# Mini-32BOT_Rev_A.net
KiCad netlist of a schematic drawn in EAGLE
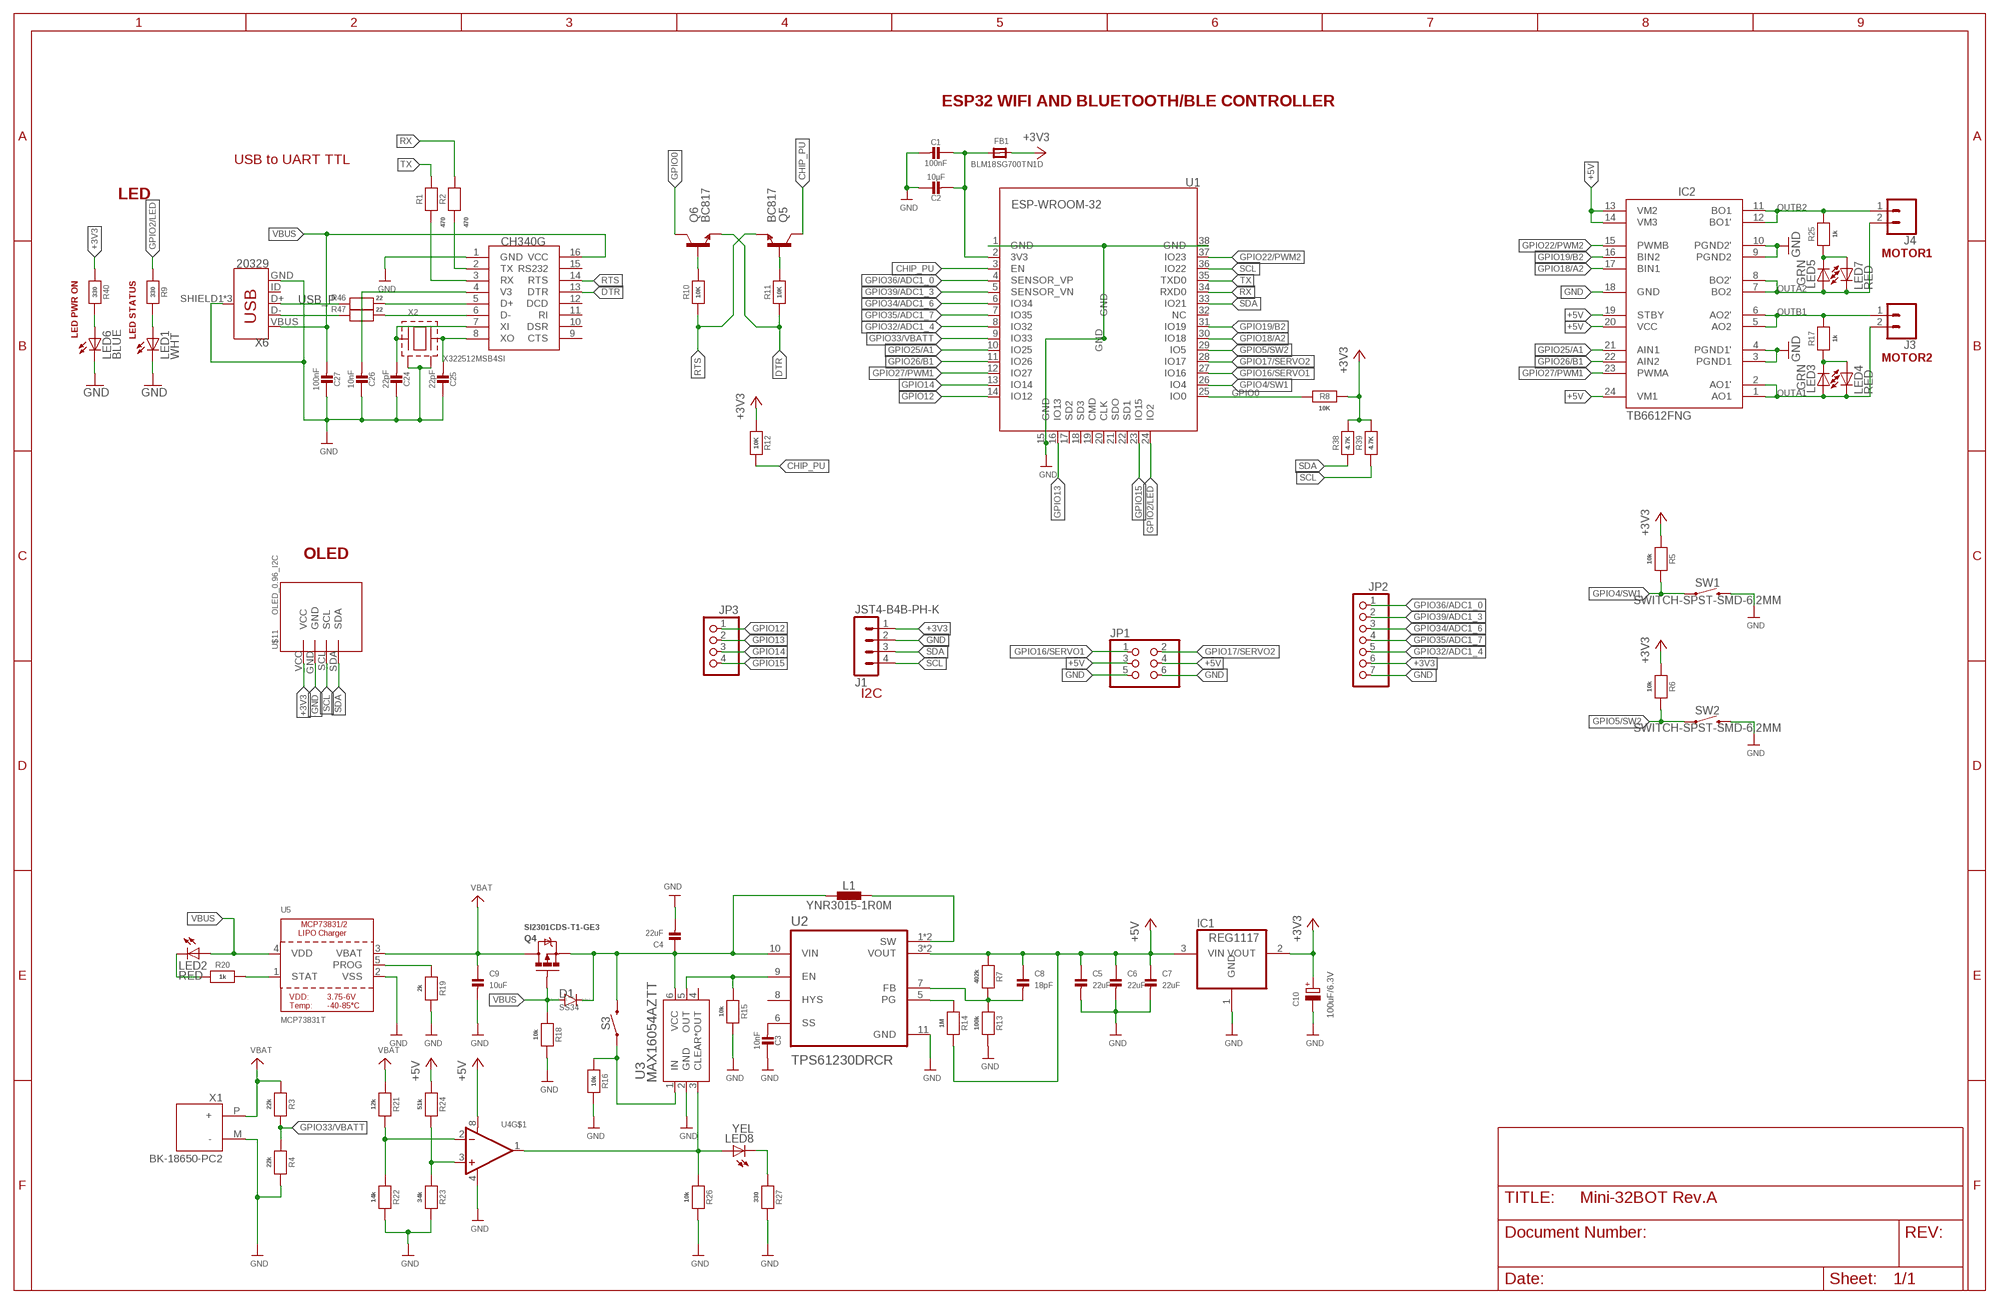
[diagram p0: schematic, sheet 1]

(export (version "E")
  (design (tool "Eeschema 10.0.6"))
  (components
    (comp (ref "C1")
      (value "100nF")
      (footprint "eagle-import:0603")
      (libsource (lib "eagle-import") (part "CAP_CERAMIC0603"))
    )
    (comp (ref "C2")
      (value "10µF")
      (footprint "eagle-import:0805")
      (libsource (lib "eagle-import") (part "CAP_CERAMIC0805"))
    )
    (comp (ref "C3")
      (value "10nF")
      (footprint "eagle-import:0603")
      (libsource (lib "eagle-import") (part "CAP_CERAMIC0603"))
    )
    (comp (ref "C4")
      (value "22uF")
      (footprint "eagle-import:0805")
      (libsource (lib "eagle-import") (part "CAP_CERAMIC0805"))
    )
    (comp (ref "C5")
      (value "22uF")
      (footprint "eagle-import:0805")
      (libsource (lib "eagle-import") (part "CAP_CERAMIC0805"))
    )
    (comp (ref "C6")
      (value "22uF")
      (footprint "eagle-import:0805")
      (libsource (lib "eagle-import") (part "CAP_CERAMIC0805"))
    )
    (comp (ref "C7")
      (value "22uF")
      (footprint "eagle-import:0805")
      (libsource (lib "eagle-import") (part "CAP_CERAMIC0805"))
    )
    (comp (ref "C8")
      (value "18pF")
      (footprint "eagle-import:0603")
      (libsource (lib "eagle-import") (part "CAP_CERAMIC0603"))
    )
    (comp (ref "C9")
      (value "10uF")
      (footprint "eagle-import:0805")
      (libsource (lib "eagle-import") (part "CAP_CERAMIC0805"))
    )
    (comp (ref "C10")
      (value "100uF/6.3V")
      (footprint "eagle-import:CT3528")
      (libsource (lib "eagle-import") (part "CPOL-EUCT3528"))
    )
    (comp (ref "C24")
      (value "22pF")
      (footprint "eagle-import:0603")
      (libsource (lib "eagle-import") (part "CAP_CERAMIC0603"))
    )
    (comp (ref "C25")
      (value "22pF")
      (footprint "eagle-import:0603")
      (libsource (lib "eagle-import") (part "CAP_CERAMIC0603"))
    )
    (comp (ref "C26")
      (value "10nF")
      (footprint "eagle-import:0603")
      (libsource (lib "eagle-import") (part "CAP_CERAMIC0603"))
    )
    (comp (ref "C27")
      (value "100nF")
      (footprint "eagle-import:0603")
      (libsource (lib "eagle-import") (part "CAP_CERAMIC0603"))
    )
    (comp (ref "D1")
      (value "SS34")
      (footprint "eagle-import:DO-214AC")
      (libsource (lib "eagle-import") (part "DIODE-DO-214AC"))
    )
    (comp (ref "FB1")
      (value "BLM18SG700TN1D")
      (footprint "eagle-import:_0603")
      (libsource (lib "eagle-import") (part "FERRITE_0603"))
    )
    (comp (ref "IC1")
      (value "REG1117")
      (footprint "eagle-import:SOT223")
      (libsource (lib "eagle-import") (part "REG1117"))
    )
    (comp (ref "IC2")
      (value "TB6612FNG")
      (footprint "eagle-import:SSOP24")
      (libsource (lib "eagle-import") (part "TB6612FNG"))
    )
    (comp (ref "J1")
      (value "JST4-B4B-PH-K")
      (footprint "eagle-import:JST_B4B-PH-K")
      (libsource (lib "eagle-import") (part "JST4-B4B-PH-K"))
    )
    (comp (ref "J3")
      (value "CONN_023.5MM")
      (footprint "eagle-import:SCREWTERMINAL-3.5MM-2")
      (libsource (lib "eagle-import") (part "CONN_023.5MM"))
    )
    (comp (ref "J4")
      (value "CONN_023.5MM")
      (footprint "eagle-import:SCREWTERMINAL-3.5MM-2")
      (libsource (lib "eagle-import") (part "CONN_023.5MM"))
    )
    (comp (ref "JP1")
      (value "PINHD-2X03_2.54")
      (footprint "eagle-import:2X03")
      (libsource (lib "eagle-import") (part "PINHD-2X03_2.54"))
    )
    (comp (ref "JP2")
      (value "PINHD-1X07_2.54-S")
      (footprint "eagle-import:1X07-S")
      (libsource (lib "eagle-import") (part "PINHD-1X07_2.54-S"))
    )
    (comp (ref "JP3")
      (value "PINHD-1X04_2.54-S")
      (footprint "eagle-import:1X04-S")
      (libsource (lib "eagle-import") (part "PINHD-1X04_2.54-S"))
    )
    (comp (ref "L1")
      (value "YNR3015-1R0M")
      (footprint "eagle-import:L_NR40XX")
      (libsource (lib "eagle-import") (part "INDUCTOR-NR40XX"))
    )
    (comp (ref "LED1")
      (value "WHT")
      (footprint "eagle-import:CHIP-LED0805")
      (libsource (lib "eagle-import") (part "LEDCHIP-LED0805"))
    )
    (comp (ref "LED2")
      (value "RED")
      (footprint "eagle-import:CHIP-LED0805")
      (libsource (lib "eagle-import") (part "LEDCHIP-LED0805"))
    )
    (comp (ref "LED3")
      (value "GRN")
      (footprint "eagle-import:CHIP-LED0805")
      (libsource (lib "eagle-import") (part "LEDCHIP-LED0805"))
    )
    (comp (ref "LED4")
      (value "RED")
      (footprint "eagle-import:CHIP-LED0805")
      (libsource (lib "eagle-import") (part "LEDCHIP-LED0805"))
    )
    (comp (ref "LED5")
      (value "GRN")
      (footprint "eagle-import:CHIP-LED0805")
      (libsource (lib "eagle-import") (part "LEDCHIP-LED0805"))
    )
    (comp (ref "LED6")
      (value "BLUE")
      (footprint "eagle-import:CHIP-LED0805")
      (libsource (lib "eagle-import") (part "LEDCHIP-LED0805"))
    )
    (comp (ref "LED7")
      (value "RED")
      (footprint "eagle-import:CHIP-LED0805")
      (libsource (lib "eagle-import") (part "LEDCHIP-LED0805"))
    )
    (comp (ref "LED8")
      (value "YEL")
      (footprint "eagle-import:CHIP-LED0805")
      (libsource (lib "eagle-import") (part "LEDCHIP-LED0805"))
    )
    (comp (ref "Q4")
      (value "SI2301CDS-T1-GE3")
      (footprint "eagle-import:SOT23-3")
      (libsource (lib "eagle-import") (part "MOSFET-PCHANNELDMG2307L"))
    )
    (comp (ref "Q5")
      (value "BC817")
      (footprint "eagle-import:SOT23-3")
      (libsource (lib "eagle-import") (part "TRANSISTOR_NPNSOT23-3"))
    )
    (comp (ref "Q6")
      (value "BC817")
      (footprint "eagle-import:SOT23-3")
      (libsource (lib "eagle-import") (part "TRANSISTOR_NPNSOT23-3"))
    )
    (comp (ref "R1")
      (value "470")
      (footprint "eagle-import:0603")
      (libsource (lib "eagle-import") (part "RESISTOR0603"))
    )
    (comp (ref "R2")
      (value "470")
      (footprint "eagle-import:0603")
      (libsource (lib "eagle-import") (part "RESISTOR0603"))
    )
    (comp (ref "R3")
      (value "22k")
      (footprint "eagle-import:0603")
      (libsource (lib "eagle-import") (part "RESISTOR0603"))
    )
    (comp (ref "R4")
      (value "22k")
      (footprint "eagle-import:0603")
      (libsource (lib "eagle-import") (part "RESISTOR0603"))
    )
    (comp (ref "R5")
      (value "10k")
      (footprint "eagle-import:0603")
      (libsource (lib "eagle-import") (part "RESISTOR0603"))
    )
    (comp (ref "R6")
      (value "10k")
      (footprint "eagle-import:0603")
      (libsource (lib "eagle-import") (part "RESISTOR0603"))
    )
    (comp (ref "R7")
      (value "402k")
      (footprint "eagle-import:0603")
      (libsource (lib "eagle-import") (part "RESISTOR0603"))
    )
    (comp (ref "R8")
      (value "10K")
      (footprint "eagle-import:0603")
      (libsource (lib "eagle-import") (part "RESISTOR0603"))
    )
    (comp (ref "R9")
      (value "330")
      (footprint "eagle-import:0603")
      (libsource (lib "eagle-import") (part "RESISTOR0603"))
    )
    (comp (ref "R10")
      (value "10K")
      (footprint "eagle-import:0603")
      (libsource (lib "eagle-import") (part "RESISTOR0603"))
    )
    (comp (ref "R11")
      (value "10K")
      (footprint "eagle-import:0603")
      (libsource (lib "eagle-import") (part "RESISTOR0603"))
    )
    (comp (ref "R12")
      (value "10K")
      (footprint "eagle-import:0603")
      (libsource (lib "eagle-import") (part "RESISTOR0603"))
    )
    (comp (ref "R13")
      (value "100k")
      (footprint "eagle-import:0603")
      (libsource (lib "eagle-import") (part "RESISTOR0603"))
    )
    (comp (ref "R14")
      (value "1M")
      (footprint "eagle-import:0603")
      (libsource (lib "eagle-import") (part "RESISTOR0603"))
    )
    (comp (ref "R15")
      (value "10k")
      (footprint "eagle-import:0603")
      (libsource (lib "eagle-import") (part "RESISTOR0603"))
    )
    (comp (ref "R16")
      (value "10k")
      (footprint "eagle-import:0603")
      (libsource (lib "eagle-import") (part "RESISTOR0603"))
    )
    (comp (ref "R17")
      (value "1k")
      (footprint "eagle-import:0603")
      (libsource (lib "eagle-import") (part "RESISTOR0603"))
    )
    (comp (ref "R18")
      (value "10k")
      (footprint "eagle-import:0603")
      (libsource (lib "eagle-import") (part "RESISTOR0603"))
    )
    (comp (ref "R19")
      (value "2k")
      (footprint "eagle-import:0603")
      (libsource (lib "eagle-import") (part "RESISTOR0603"))
    )
    (comp (ref "R20")
      (value "1k")
      (footprint "eagle-import:0603")
      (libsource (lib "eagle-import") (part "RESISTOR0603"))
    )
    (comp (ref "R21")
      (value "12k")
      (footprint "eagle-import:0603")
      (libsource (lib "eagle-import") (part "RESISTOR0603"))
    )
    (comp (ref "R22")
      (value "14k")
      (footprint "eagle-import:0603")
      (libsource (lib "eagle-import") (part "RESISTOR0603"))
    )
    (comp (ref "R23")
      (value "34k")
      (footprint "eagle-import:0603")
      (libsource (lib "eagle-import") (part "RESISTOR0603"))
    )
    (comp (ref "R24")
      (value "51k")
      (footprint "eagle-import:0603")
      (libsource (lib "eagle-import") (part "RESISTOR0603"))
    )
    (comp (ref "R25")
      (value "1k")
      (footprint "eagle-import:0603")
      (libsource (lib "eagle-import") (part "RESISTOR0603"))
    )
    (comp (ref "R26")
      (value "10k")
      (footprint "eagle-import:0603")
      (libsource (lib "eagle-import") (part "RESISTOR0603"))
    )
    (comp (ref "R27")
      (value "330")
      (footprint "eagle-import:0603")
      (libsource (lib "eagle-import") (part "RESISTOR0603"))
    )
    (comp (ref "R38")
      (value "4.7K")
      (footprint "eagle-import:0603")
      (libsource (lib "eagle-import") (part "RESISTOR0603"))
    )
    (comp (ref "R39")
      (value "4.7K")
      (footprint "eagle-import:0603")
      (libsource (lib "eagle-import") (part "RESISTOR0603"))
    )
    (comp (ref "R40")
      (value "330")
      (footprint "eagle-import:0603")
      (libsource (lib "eagle-import") (part "RESISTOR0603"))
    )
    (comp (ref "R46")
      (value "22")
      (footprint "eagle-import:0603")
      (libsource (lib "eagle-import") (part "RESISTOR0603"))
    )
    (comp (ref "R47")
      (value "22")
      (footprint "eagle-import:0603")
      (libsource (lib "eagle-import") (part "RESISTOR0603"))
    )
    (comp (ref "S3")
      (value "MOMENTARY-SWITCH-SPST-PTH-RIGHT-ANGLE-KIT")
      (footprint "eagle-import:TACTILE_SWITCH_PTH_RIGHT_ANGLE_KIT")
      (libsource (lib "eagle-import") (part "MOMENTARY-SWITCH-SPST-PTH-RIGHT-ANGLE-KIT"))
    )
    (comp (ref "SW1")
      (value "SWITCH-SPST-SMD-6.2MM")
      (footprint "eagle-import:TACTILE_SWITCH_SMD_6.2MM_TALL")
      (libsource (lib "eagle-import") (part "MOMENTARY-SWITCH-SPST-SMD-6.2MM-TALL"))
    )
    (comp (ref "SW2")
      (value "SWITCH-SPST-SMD-6.2MM")
      (footprint "eagle-import:TACTILE_SWITCH_SMD_6.2MM_TALL")
      (libsource (lib "eagle-import") (part "MOMENTARY-SWITCH-SPST-SMD-6.2MM-TALL"))
    )
    (comp (ref "U$11")
      (value "OLED_0.96_I2C")
      (footprint "eagle-import:OLED_0.96_I2C")
      (libsource (lib "eagle-import") (part "OLED_0.96_I2C"))
    )
    (comp (ref "U$24")
      (value "CH340G")
      (footprint "eagle-import:SOIC16")
      (libsource (lib "eagle-import") (part "CH340G"))
    )
    (comp (ref "U1")
      (value "ESP-WROOM-32")
      (footprint "eagle-import:ESP-WROOM-32")
      (libsource (lib "eagle-import") (part "ESP-WROOM-32"))
    )
    (comp (ref "U2")
      (value "TPS61230DRCR")
      (footprint "eagle-import:SON50P300X300X100-11N")
      (fields (field (name "MF") "Texas Instruments"))
      (libsource (lib "eagle-import") (part "TPS61230DRCR"))
    )
    (comp (ref "U3")
      (value "MAX16054AZTT")
      (footprint "eagle-import:21-0114C")
      (fields (field (name "MF") "Maxim Integrated") (field (name "MP") "MAX16054AZT+"))
      (libsource (lib "eagle-import") (part "MAX16054AZTT"))
    )
    (comp (ref "U4")
      (value "LM358")
      (footprint "eagle-import:SOIC8_150MIL")
      (libsource (lib "eagle-import") (part "LM358"))
    )
    (comp (ref "U5")
      (value "MCP73831T")
      (footprint "eagle-import:SOT23-5")
      (libsource (lib "eagle-import") (part "MCP73831/2"))
    )
    (comp (ref "X1")
      (value "BK-18650-PC2")
      (footprint "eagle-import:MPD_BK-18650-PC2")
      (fields (field (name "MF") "MPD _Memory"))
      (libsource (lib "eagle-import") (part "BK-18650-PC2"))
    )
    (comp (ref "X2")
      (value "X322512MSB4SI")
      (footprint "eagle-import:X3225_4P")
      (libsource (lib "eagle-import") (part "306010049_XTAL_16MHZ-3225_4P"))
    )
    (comp (ref "X6")
      (value "20329")
      (footprint "eagle-import:USB-B-MICRO-SMD")
      (libsource (lib "eagle-import") (part "USB_MICRO-B_FEMALE-SMT"))
    )
  )
  (nets
    (net (code "1") (name "+3V3") (class "Default")
      (node (ref "C10") (pin "+") (pinfunction "+_+") (pintype "passive"))
      (node (ref "FB1") (pin "2") (pinfunction "P$2_2") (pintype "passive"))
      (node (ref "IC1") (pin "2") (pinfunction "VOUT_2") (pintype "output"))
      (node (ref "J1") (pin "1") (pinfunction "1_1") (pintype "passive"))
      (node (ref "JP2") (pin "6") (pinfunction "6_6") (pintype "passive"))
      (node (ref "R12") (pin "1") (pinfunction "1_1") (pintype "passive"))
      (node (ref "R38") (pin "2") (pinfunction "2_2") (pintype "passive"))
      (node (ref "R39") (pin "2") (pinfunction "2_2") (pintype "passive"))
      (node (ref "R40") (pin "1") (pinfunction "1_1") (pintype "passive"))
      (node (ref "R5") (pin "1") (pinfunction "1_1") (pintype "passive"))
      (node (ref "R6") (pin "1") (pinfunction "1_1") (pintype "passive"))
      (node (ref "R8") (pin "2") (pinfunction "2_2") (pintype "passive"))
      (node (ref "U$11") (pin "VCC") (pinfunction "VCC_VCC") (pintype "bidirectional"))
    )
    (net (code "2") (name "+5V") (class "Default")
      (node (ref "C5") (pin "1") (pinfunction "P$1_1") (pintype "passive"))
      (node (ref "C6") (pin "1") (pinfunction "P$1_1") (pintype "passive"))
      (node (ref "C7") (pin "1") (pinfunction "P$1_1") (pintype "passive"))
      (node (ref "C8") (pin "1") (pinfunction "P$1_1") (pintype "passive"))
      (node (ref "IC1") (pin "3") (pinfunction "VIN_3") (pintype "input"))
      (node (ref "IC2") (pin "13") (pinfunction "VM2_13") (pintype "power_in"))
      (node (ref "IC2") (pin "14") (pinfunction "VM3_14") (pintype "power_in"))
      (node (ref "IC2") (pin "19") (pinfunction "STBY_19") (pintype "input"))
      (node (ref "IC2") (pin "20") (pinfunction "VCC_20") (pintype "power_in"))
      (node (ref "IC2") (pin "24") (pinfunction "VM1_24") (pintype "power_in"))
      (node (ref "JP1") (pin "3") (pinfunction "3_3") (pintype "passive"))
      (node (ref "JP1") (pin "4") (pinfunction "4_4") (pintype "passive"))
      (node (ref "R14") (pin "2") (pinfunction "2_2") (pintype "passive"))
      (node (ref "R24") (pin "1") (pinfunction "1_1") (pintype "passive"))
      (node (ref "R7") (pin "1") (pinfunction "1_1") (pintype "passive"))
      (node (ref "U2") (pin "3") (pinfunction "VOUT_3") (pintype "output"))
      (node (ref "U2") (pin "4") (pinfunction "VOUT_4") (pintype "output"))
      (node (ref "U4") (pin "8") (pinfunction "V+_8") (pintype "power_in"))
    )
    (net (code "3") (name "/OUTA1") (class "Default")
      (node (ref "IC2") (pin "1") (pinfunction "AO1_1") (pintype "output"))
      (node (ref "IC2") (pin "2") (pinfunction "AO1'_2") (pintype "output"))
      (node (ref "J3") (pin "2") (pinfunction "2_2") (pintype "passive"))
      (node (ref "LED3") (pin "A") (pinfunction "A_A") (pintype "passive"))
      (node (ref "LED4") (pin "C") (pinfunction "C_C") (pintype "passive"))
    )
    (net (code "4") (name "/OUTA2") (class "Default")
      (node (ref "IC2") (pin "7") (pinfunction "BO2_7") (pintype "output"))
      (node (ref "IC2") (pin "8") (pinfunction "BO2'_8") (pintype "output"))
      (node (ref "J4") (pin "2") (pinfunction "2_2") (pintype "passive"))
      (node (ref "LED5") (pin "A") (pinfunction "A_A") (pintype "passive"))
      (node (ref "LED7") (pin "C") (pinfunction "C_C") (pintype "passive"))
    )
    (net (code "5") (name "/OUTB1") (class "Default")
      (node (ref "IC2") (pin "5") (pinfunction "AO2_5") (pintype "output"))
      (node (ref "IC2") (pin "6") (pinfunction "AO2'_6") (pintype "output"))
      (node (ref "J3") (pin "1") (pinfunction "1_1") (pintype "passive"))
      (node (ref "R17") (pin "2") (pinfunction "2_2") (pintype "passive"))
    )
    (net (code "6") (name "/OUTB2") (class "Default")
      (node (ref "IC2") (pin "11") (pinfunction "BO1_11") (pintype "output"))
      (node (ref "IC2") (pin "12") (pinfunction "BO1'_12") (pintype "output"))
      (node (ref "J4") (pin "1") (pinfunction "1_1") (pintype "passive"))
      (node (ref "R25") (pin "2") (pinfunction "2_2") (pintype "passive"))
    )
    (net (code "7") (name "/USB_P") (class "Default")
      (node (ref "R46") (pin "2") (pinfunction "2_2") (pintype "passive"))
      (node (ref "X6") (pin "D+") (pinfunction "D+_D+") (pintype "bidirectional"))
    )
    (net (code "8") (name "CHIP_PU") (class "Default")
      (node (ref "Q5") (pin "3") (pinfunction "C_3") (pintype "passive"))
      (node (ref "R12") (pin "2") (pinfunction "2_2") (pintype "passive"))
      (node (ref "U1") (pin "3") (pinfunction "EN_3") (pintype "bidirectional"))
    )
    (net (code "9") (name "DTR") (class "Default")
      (node (ref "Q6") (pin "2") (pinfunction "E_2") (pintype "passive"))
      (node (ref "R11") (pin "1") (pinfunction "1_1") (pintype "passive"))
      (node (ref "U$24") (pin "13") (pinfunction "DTR_13") (pintype "bidirectional"))
    )
    (net (code "10") (name "GND") (class "Default")
      (node (ref "C1") (pin "2") (pinfunction "P$2_2") (pintype "passive"))
      (node (ref "C10") (pin "-") (pinfunction "-_-") (pintype "passive"))
      (node (ref "C2") (pin "1") (pinfunction "P$1_1") (pintype "passive"))
      (node (ref "C24") (pin "1") (pinfunction "P$1_1") (pintype "passive"))
      (node (ref "C25") (pin "1") (pinfunction "P$1_1") (pintype "passive"))
      (node (ref "C26") (pin "1") (pinfunction "P$1_1") (pintype "passive"))
      (node (ref "C27") (pin "1") (pinfunction "P$1_1") (pintype "passive"))
      (node (ref "C3") (pin "1") (pinfunction "P$1_1") (pintype "passive"))
      (node (ref "C4") (pin "2") (pinfunction "P$2_2") (pintype "passive"))
      (node (ref "C5") (pin "2") (pinfunction "P$2_2") (pintype "passive"))
      (node (ref "C6") (pin "2") (pinfunction "P$2_2") (pintype "passive"))
      (node (ref "C7") (pin "2") (pinfunction "P$2_2") (pintype "passive"))
      (node (ref "C9") (pin "2") (pinfunction "P$2_2") (pintype "passive"))
      (node (ref "IC1") (pin "1") (pinfunction "GND_1") (pintype "power_in"))
      (node (ref "IC2") (pin "10") (pinfunction "PGND2'_10") (pintype "power_in"))
      (node (ref "IC2") (pin "18") (pinfunction "GND_18") (pintype "power_in"))
      (node (ref "IC2") (pin "3") (pinfunction "PGND1_3") (pintype "power_in"))
      (node (ref "IC2") (pin "4") (pinfunction "PGND1'_4") (pintype "power_in"))
      (node (ref "IC2") (pin "9") (pinfunction "PGND2_9") (pintype "power_in"))
      (node (ref "J1") (pin "2") (pinfunction "2_2") (pintype "passive"))
      (node (ref "JP1") (pin "5") (pinfunction "5_5") (pintype "passive"))
      (node (ref "JP1") (pin "6") (pinfunction "6_6") (pintype "passive"))
      (node (ref "JP2") (pin "7") (pinfunction "7_7") (pintype "passive"))
      (node (ref "LED1") (pin "C") (pinfunction "C_C") (pintype "passive"))
      (node (ref "LED6") (pin "C") (pinfunction "C_C") (pintype "passive"))
      (node (ref "R13") (pin "2") (pinfunction "2_2") (pintype "passive"))
      (node (ref "R15") (pin "2") (pinfunction "2_2") (pintype "passive"))
      (node (ref "R16") (pin "2") (pinfunction "2_2") (pintype "passive"))
      (node (ref "R18") (pin "2") (pinfunction "2_2") (pintype "passive"))
      (node (ref "R19") (pin "2") (pinfunction "2_2") (pintype "passive"))
      (node (ref "R22") (pin "2") (pinfunction "2_2") (pintype "passive"))
      (node (ref "R23") (pin "2") (pinfunction "2_2") (pintype "passive"))
      (node (ref "R26") (pin "2") (pinfunction "2_2") (pintype "passive"))
      (node (ref "R27") (pin "2") (pinfunction "2_2") (pintype "passive"))
      (node (ref "R4") (pin "2") (pinfunction "2_2") (pintype "passive"))
      (node (ref "SW1") (pin "B2") (pinfunction "2_B2") (pintype "passive"))
      (node (ref "SW2") (pin "B2") (pinfunction "2_B2") (pintype "passive"))
      (node (ref "U$11") (pin "GND") (pinfunction "GND_GND") (pintype "bidirectional"))
      (node (ref "U$24") (pin "1") (pinfunction "GND_1") (pintype "bidirectional"))
      (node (ref "U1") (pin "1") (pinfunction "GND_1") (pintype "bidirectional"))
      (node (ref "U1") (pin "15") (pinfunction "GND_15") (pintype "bidirectional"))
      (node (ref "U1") (pin "38") (pinfunction "GND_38") (pintype "bidirectional"))
      (node (ref "U1") (pin "GND") (pinfunction "GND_GND") (pintype "bidirectional"))
      (node (ref "U2") (pin "11") (pinfunction "GND_11") (pintype "power_in"))
      (node (ref "U3") (pin "2") (pinfunction "GND_2") (pintype "power_in"))
      (node (ref "U4") (pin "4") (pinfunction "V-_4") (pintype "power_in"))
      (node (ref "U5") (pin "2") (pinfunction "VSS_2") (pintype "power_in"))
      (node (ref "X1") (pin "M") (pinfunction "-_M") (pintype "passive"))
      (node (ref "X2") (pin "P$2") (pinfunction "GND1_P$2") (pintype "power_in"))
      (node (ref "X2") (pin "P$4") (pinfunction "GND2_P$4") (pintype "power_in"))
      (node (ref "X6") (pin "GND") (pinfunction "GND_GND") (pintype "power_in"))
      (node (ref "X6") (pin "SHIELD1") (pinfunction "SHIELD_SHIELD1") (pintype "bidirectional"))
      (node (ref "X6") (pin "SHIELD2") (pinfunction "SHIELD_SHIELD2") (pintype "bidirectional"))
      (node (ref "X6") (pin "SHIELD3") (pinfunction "SHIELD_SHIELD3") (pintype "bidirectional"))
    )
    (net (code "11") (name "GPIO0") (class "Default")
      (node (ref "Q6") (pin "3") (pinfunction "C_3") (pintype "passive"))
      (node (ref "R8") (pin "1") (pinfunction "1_1") (pintype "passive"))
      (node (ref "U1") (pin "25") (pinfunction "IO0_25") (pintype "bidirectional"))
    )
    (net (code "12") (name "GPIO2{slash}LED") (class "Default")
      (node (ref "R9") (pin "1") (pinfunction "1_1") (pintype "passive"))
      (node (ref "U1") (pin "24") (pinfunction "IO2_24") (pintype "bidirectional"))
    )
    (net (code "13") (name "GPIO4{slash}SW1") (class "Default")
      (node (ref "R5") (pin "2") (pinfunction "2_2") (pintype "passive"))
      (node (ref "SW1") (pin "A2") (pinfunction "1_A2") (pintype "passive"))
      (node (ref "U1") (pin "26") (pinfunction "IO4_26") (pintype "bidirectional"))
    )
    (net (code "14") (name "GPIO5{slash}SW2") (class "Default")
      (node (ref "R6") (pin "2") (pinfunction "2_2") (pintype "passive"))
      (node (ref "SW2") (pin "A2") (pinfunction "1_A2") (pintype "passive"))
      (node (ref "U1") (pin "29") (pinfunction "IO5_29") (pintype "bidirectional"))
    )
    (net (code "15") (name "GPIO12") (class "Default")
      (node (ref "JP3") (pin "1") (pinfunction "1_1") (pintype "passive"))
      (node (ref "U1") (pin "14") (pinfunction "IO12_14") (pintype "bidirectional"))
    )
    (net (code "16") (name "GPIO13") (class "Default")
      (node (ref "JP3") (pin "2") (pinfunction "2_2") (pintype "passive"))
      (node (ref "U1") (pin "16") (pinfunction "IO13_16") (pintype "bidirectional"))
    )
    (net (code "17") (name "GPIO14") (class "Default")
      (node (ref "JP3") (pin "3") (pinfunction "3_3") (pintype "passive"))
      (node (ref "U1") (pin "13") (pinfunction "IO14_13") (pintype "bidirectional"))
    )
    (net (code "18") (name "GPIO15") (class "Default")
      (node (ref "JP3") (pin "4") (pinfunction "4_4") (pintype "passive"))
      (node (ref "U1") (pin "23") (pinfunction "IO15_23") (pintype "bidirectional"))
    )
    (net (code "19") (name "GPIO16{slash}SERVO1") (class "Default")
      (node (ref "JP1") (pin "1") (pinfunction "1_1") (pintype "passive"))
      (node (ref "U1") (pin "27") (pinfunction "IO16_27") (pintype "bidirectional"))
    )
    (net (code "20") (name "GPIO17{slash}SERVO2") (class "Default")
      (node (ref "JP1") (pin "2") (pinfunction "2_2") (pintype "passive"))
      (node (ref "U1") (pin "28") (pinfunction "IO17_28") (pintype "bidirectional"))
    )
    (net (code "21") (name "GPIO18{slash}A2") (class "Default")
      (node (ref "IC2") (pin "17") (pinfunction "BIN1_17") (pintype "input"))
      (node (ref "U1") (pin "30") (pinfunction "IO18_30") (pintype "bidirectional"))
    )
    (net (code "22") (name "GPIO19{slash}B2") (class "Default")
      (node (ref "IC2") (pin "16") (pinfunction "BIN2_16") (pintype "input"))
      (node (ref "U1") (pin "31") (pinfunction "IO19_31") (pintype "bidirectional"))
    )
    (net (code "23") (name "GPIO22{slash}PWM2") (class "Default")
      (node (ref "IC2") (pin "15") (pinfunction "PWMB_15") (pintype "input"))
      (node (ref "U1") (pin "37") (pinfunction "IO23_37") (pintype "bidirectional"))
    )
    (net (code "24") (name "GPIO25{slash}A1") (class "Default")
      (node (ref "IC2") (pin "21") (pinfunction "AIN1_21") (pintype "input"))
      (node (ref "U1") (pin "10") (pinfunction "IO25_10") (pintype "bidirectional"))
    )
    (net (code "25") (name "GPIO26{slash}B1") (class "Default")
      (node (ref "IC2") (pin "22") (pinfunction "AIN2_22") (pintype "input"))
      (node (ref "U1") (pin "11") (pinfunction "IO26_11") (pintype "bidirectional"))
    )
    (net (code "26") (name "GPIO27{slash}PWM1") (class "Default")
      (node (ref "IC2") (pin "23") (pinfunction "PWMA_23") (pintype "input"))
      (node (ref "U1") (pin "12") (pinfunction "IO27_12") (pintype "bidirectional"))
    )
    (net (code "27") (name "GPIO32{slash}ADC1_4") (class "Default")
      (node (ref "JP2") (pin "5") (pinfunction "5_5") (pintype "passive"))
      (node (ref "U1") (pin "8") (pinfunction "IO32_8") (pintype "bidirectional"))
    )
    (net (code "28") (name "GPIO33{slash}VBATT") (class "Default")
      (node (ref "R3") (pin "2") (pinfunction "2_2") (pintype "passive"))
      (node (ref "R4") (pin "1") (pinfunction "1_1") (pintype "passive"))
      (node (ref "U1") (pin "9") (pinfunction "IO33_9") (pintype "bidirectional"))
    )
    (net (code "29") (name "GPIO34{slash}ADC1_6") (class "Default")
      (node (ref "JP2") (pin "3") (pinfunction "3_3") (pintype "passive"))
      (node (ref "U1") (pin "6") (pinfunction "IO34_6") (pintype "bidirectional"))
    )
    (net (code "30") (name "GPIO35{slash}ADC1_7") (class "Default")
      (node (ref "JP2") (pin "4") (pinfunction "4_4") (pintype "passive"))
      (node (ref "U1") (pin "7") (pinfunction "IO35_7") (pintype "bidirectional"))
    )
    (net (code "31") (name "GPIO36{slash}ADC1_0") (class "Default")
      (node (ref "JP2") (pin "1") (pinfunction "1_1") (pintype "passive"))
      (node (ref "U1") (pin "4") (pinfunction "SENSOR_VP_4") (pintype "bidirectional"))
    )
    (net (code "32") (name "GPIO39{slash}ADC1_3") (class "Default")
      (node (ref "JP2") (pin "2") (pinfunction "2_2") (pintype "passive"))
      (node (ref "U1") (pin "5") (pinfunction "SENSOR_VN_5") (pintype "bidirectional"))
    )
    (net (code "33") (name "Net-(C1-P$1)") (class "Default")
      (node (ref "C1") (pin "1") (pinfunction "P$1_1") (pintype "passive"))
      (node (ref "C2") (pin "2") (pinfunction "P$2_2") (pintype "passive"))
      (node (ref "FB1") (pin "1") (pinfunction "P$1_1") (pintype "passive"))
      (node (ref "U1") (pin "2") (pinfunction "3V3_2") (pintype "bidirectional"))
    )
    (net (code "34") (name "Net-(C3-P$2)") (class "Default")
      (node (ref "C3") (pin "2") (pinfunction "P$2_2") (pintype "passive"))
      (node (ref "U2") (pin "6") (pinfunction "SS_6") (pintype "input"))
    )
    (net (code "35") (name "Net-(C4-P$1)") (class "Default")
      (node (ref "C4") (pin "1") (pinfunction "P$1_1") (pintype "passive"))
      (node (ref "D1") (pin "C") (pinfunction "C_C") (pintype "passive"))
      (node (ref "L1") (pin "1") (pinfunction "1_1") (pintype "passive"))
      (node (ref "Q4") (pin "2") (pinfunction "S_2") (pintype "passive"))
      (node (ref "S3") (pin "2") (pinfunction "2_2") (pintype "passive"))
      (node (ref "U2") (pin "10") (pinfunction "VIN_10") (pintype "input"))
      (node (ref "U3") (pin "6") (pinfunction "VCC_6") (pintype "power_in"))
    )
    (net (code "36") (name "Net-(C8-P$2)") (class "Default")
      (node (ref "C8") (pin "2") (pinfunction "P$2_2") (pintype "passive"))
      (node (ref "R13") (pin "1") (pinfunction "1_1") (pintype "passive"))
      (node (ref "R7") (pin "2") (pinfunction "2_2") (pintype "passive"))
      (node (ref "U2") (pin "7") (pinfunction "FB_7") (pintype "input"))
    )
    (net (code "37") (name "Net-(C24-P$2)") (class "Default")
      (node (ref "C24") (pin "2") (pinfunction "P$2_2") (pintype "passive"))
      (node (ref "U$24") (pin "7") (pinfunction "XI_7") (pintype "bidirectional"))
      (node (ref "X2") (pin "P$1") (pinfunction "P$1_P$1") (pintype "passive"))
    )
    (net (code "38") (name "Net-(C25-P$2)") (class "Default")
      (node (ref "C25") (pin "2") (pinfunction "P$2_2") (pintype "passive"))
      (node (ref "U$24") (pin "8") (pinfunction "XO_8") (pintype "bidirectional"))
      (node (ref "X2") (pin "P$3") (pinfunction "P$2_P$3") (pintype "passive"))
    )
    (net (code "39") (name "Net-(C26-P$2)") (class "Default")
      (node (ref "C26") (pin "2") (pinfunction "P$2_2") (pintype "passive"))
      (node (ref "U$24") (pin "4") (pinfunction "V3_4") (pintype "bidirectional"))
    )
    (net (code "40") (name "Net-(L1-Pad2)") (class "Default")
      (node (ref "L1") (pin "2") (pinfunction "2_2") (pintype "passive"))
      (node (ref "U2") (pin "1") (pinfunction "SW_1") (pintype "output"))
      (node (ref "U2") (pin "2") (pinfunction "SW_2") (pintype "output"))
    )
    (net (code "41") (name "Net-(LED1-PadA)") (class "Default")
      (node (ref "LED1") (pin "A") (pinfunction "A_A") (pintype "passive"))
      (node (ref "R9") (pin "2") (pinfunction "2_2") (pintype "passive"))
    )
    (net (code "42") (name "Net-(LED2-PadC)") (class "Default")
      (node (ref "LED2") (pin "C") (pinfunction "C_C") (pintype "passive"))
      (node (ref "R20") (pin "1") (pinfunction "1_1") (pintype "passive"))
    )
    (net (code "43") (name "Net-(LED3-PadC)") (class "Default")
      (node (ref "LED3") (pin "C") (pinfunction "C_C") (pintype "passive"))
      (node (ref "LED4") (pin "A") (pinfunction "A_A") (pintype "passive"))
      (node (ref "R17") (pin "1") (pinfunction "1_1") (pintype "passive"))
    )
    (net (code "44") (name "Net-(LED5-PadC)") (class "Default")
      (node (ref "LED5") (pin "C") (pinfunction "C_C") (pintype "passive"))
      (node (ref "LED7") (pin "A") (pinfunction "A_A") (pintype "passive"))
      (node (ref "R25") (pin "1") (pinfunction "1_1") (pintype "passive"))
    )
    (net (code "45") (name "Net-(LED6-PadA)") (class "Default")
      (node (ref "LED6") (pin "A") (pinfunction "A_A") (pintype "passive"))
      (node (ref "R40") (pin "2") (pinfunction "2_2") (pintype "passive"))
    )
    (net (code "46") (name "Net-(LED8-PadC)") (class "Default")
      (node (ref "LED8") (pin "C") (pinfunction "C_C") (pintype "passive"))
      (node (ref "R27") (pin "1") (pinfunction "1_1") (pintype "passive"))
    )
    (net (code "47") (name "Net-(Q5-B)") (class "Default")
      (node (ref "Q5") (pin "1") (pinfunction "B_1") (pintype "passive"))
      (node (ref "R11") (pin "2") (pinfunction "2_2") (pintype "passive"))
    )
    (net (code "48") (name "Net-(Q6-B)") (class "Default")
      (node (ref "Q6") (pin "1") (pinfunction "B_1") (pintype "passive"))
      (node (ref "R10") (pin "2") (pinfunction "2_2") (pintype "passive"))
    )
    (net (code "49") (name "Net-(R47-Pad2)") (class "Default")
      (node (ref "R47") (pin "2") (pinfunction "2_2") (pintype "passive"))
      (node (ref "X6") (pin "D-") (pinfunction "D-_D-") (pintype "bidirectional"))
    )
    (net (code "50") (name "Net-(U$24-D+)") (class "Default")
      (node (ref "R46") (pin "1") (pinfunction "1_1") (pintype "passive"))
      (node (ref "U$24") (pin "5") (pinfunction "D+_5") (pintype "bidirectional"))
    )
    (net (code "51") (name "Net-(U$24-D-)") (class "Default")
      (node (ref "R47") (pin "1") (pinfunction "1_1") (pintype "passive"))
      (node (ref "U$24") (pin "6") (pinfunction "D-_6") (pintype "bidirectional"))
    )
    (net (code "52") (name "Net-(U$24-RX)") (class "Default")
      (node (ref "R1") (pin "1") (pinfunction "1_1") (pintype "passive"))
      (node (ref "U$24") (pin "3") (pinfunction "RX_3") (pintype "bidirectional"))
    )
    (net (code "53") (name "Net-(U$24-TX)") (class "Default")
      (node (ref "R2") (pin "1") (pinfunction "1_1") (pintype "passive"))
      (node (ref "U$24") (pin "2") (pinfunction "TX_2") (pintype "bidirectional"))
    )
    (net (code "54") (name "Net-(U2-EN)") (class "Default")
      (node (ref "R15") (pin "1") (pinfunction "1_1") (pintype "passive"))
      (node (ref "U2") (pin "9") (pinfunction "EN_9") (pintype "input"))
      (node (ref "U3") (pin "5") (pinfunction "OUT_5") (pintype "output"))
    )
    (net (code "55") (name "Net-(U2-PG)") (class "Default")
      (node (ref "R14") (pin "1") (pinfunction "1_1") (pintype "passive"))
      (node (ref "U2") (pin "5") (pinfunction "PG_5") (pintype "output"))
    )
    (net (code "56") (name "Net-(U3-CLEAR)") (class "Default")
      (node (ref "LED8") (pin "A") (pinfunction "A_A") (pintype "passive"))
      (node (ref "R26") (pin "1") (pinfunction "1_1") (pintype "passive"))
      (node (ref "U3") (pin "3") (pinfunction "CLEAR_3") (pintype "bidirectional"))
      (node (ref "U4") (pin "1") (pinfunction "OUT_1") (pintype "output"))
    )
    (net (code "57") (name "Net-(U3-IN)") (class "Default")
      (node (ref "R16") (pin "1") (pinfunction "1_1") (pintype "passive"))
      (node (ref "S3") (pin "1") (pinfunction "1_1") (pintype "passive"))
      (node (ref "U3") (pin "1") (pinfunction "IN_1") (pintype "input"))
    )
    (net (code "58") (name "Net-(U4A-+IN)") (class "Default")
      (node (ref "R23") (pin "1") (pinfunction "1_1") (pintype "passive"))
      (node (ref "R24") (pin "2") (pinfunction "2_2") (pintype "passive"))
      (node (ref "U4") (pin "3") (pinfunction "+IN_3") (pintype "input"))
    )
    (net (code "59") (name "Net-(U4A--IN)") (class "Default")
      (node (ref "R21") (pin "2") (pinfunction "2_2") (pintype "passive"))
      (node (ref "R22") (pin "1") (pinfunction "1_1") (pintype "passive"))
      (node (ref "U4") (pin "2") (pinfunction "-IN_2") (pintype "input"))
    )
    (net (code "60") (name "Net-(U5-PROG)") (class "Default")
      (node (ref "R19") (pin "1") (pinfunction "1_1") (pintype "passive"))
      (node (ref "U5") (pin "5") (pinfunction "PROG_5") (pintype "input"))
    )
    (net (code "61") (name "Net-(U5-STAT)") (class "Default")
      (node (ref "R20") (pin "2") (pinfunction "2_2") (pintype "passive"))
      (node (ref "U5") (pin "1") (pinfunction "STAT_1") (pintype "output"))
    )
    (net (code "62") (name "RTS") (class "Default")
      (node (ref "Q5") (pin "2") (pinfunction "E_2") (pintype "passive"))
      (node (ref "R10") (pin "1") (pinfunction "1_1") (pintype "passive"))
      (node (ref "U$24") (pin "14") (pinfunction "RTS_14") (pintype "bidirectional"))
    )
    (net (code "63") (name "RX") (class "Default")
      (node (ref "R2") (pin "2") (pinfunction "2_2") (pintype "passive"))
      (node (ref "U1") (pin "34") (pinfunction "RXD0_34") (pintype "bidirectional"))
    )
    (net (code "64") (name "SCL") (class "Default")
      (node (ref "J1") (pin "4") (pinfunction "4_4") (pintype "passive"))
      (node (ref "R39") (pin "1") (pinfunction "1_1") (pintype "passive"))
      (node (ref "U$11") (pin "SCL") (pinfunction "SCL_SCL") (pintype "bidirectional"))
      (node (ref "U1") (pin "36") (pinfunction "IO22_36") (pintype "bidirectional"))
    )
    (net (code "65") (name "SDA") (class "Default")
      (node (ref "J1") (pin "3") (pinfunction "3_3") (pintype "passive"))
      (node (ref "R38") (pin "1") (pinfunction "1_1") (pintype "passive"))
      (node (ref "U$11") (pin "SDA") (pinfunction "SDA_SDA") (pintype "bidirectional"))
      (node (ref "U1") (pin "33") (pinfunction "IO21_33") (pintype "bidirectional"))
    )
    (net (code "66") (name "TX") (class "Default")
      (node (ref "R1") (pin "2") (pinfunction "2_2") (pintype "passive"))
      (node (ref "U1") (pin "35") (pinfunction "TXD0_35") (pintype "bidirectional"))
    )
    (net (code "67") (name "VBAT") (class "Default")
      (node (ref "C9") (pin "1") (pinfunction "P$1_1") (pintype "passive"))
      (node (ref "Q4") (pin "3") (pinfunction "D_3") (pintype "passive"))
      (node (ref "R21") (pin "1") (pinfunction "1_1") (pintype "passive"))
      (node (ref "R3") (pin "1") (pinfunction "1_1") (pintype "passive"))
      (node (ref "U5") (pin "3") (pinfunction "VBAT_3") (pintype "power_in"))
      (node (ref "X1") (pin "P") (pinfunction "+_P") (pintype "passive"))
    )
    (net (code "68") (name "VBUS") (class "Default")
      (node (ref "C27") (pin "2") (pinfunction "P$2_2") (pintype "passive"))
      (node (ref "D1") (pin "A") (pinfunction "A_A") (pintype "passive"))
      (node (ref "LED2") (pin "A") (pinfunction "A_A") (pintype "passive"))
      (node (ref "Q4") (pin "1") (pinfunction "G_1") (pintype "passive"))
      (node (ref "R18") (pin "1") (pinfunction "1_1") (pintype "passive"))
      (node (ref "U$24") (pin "16") (pinfunction "VCC_16") (pintype "bidirectional"))
      (node (ref "U5") (pin "4") (pinfunction "VDD_4") (pintype "power_in"))
      (node (ref "X6") (pin "VBUS") (pinfunction "VBUS_VBUS") (pintype "power_in"))
    )
    (net (code "69") (name "unconnected-(U$24-CTS-Pad9)") (class "Default")
      (node (ref "U$24") (pin "9") (pinfunction "CTS_9") (pintype "bidirectional"))
    )
    (net (code "70") (name "unconnected-(U$24-DCD-Pad12)") (class "Default")
      (node (ref "U$24") (pin "12") (pinfunction "DCD_12") (pintype "bidirectional"))
    )
    (net (code "71") (name "unconnected-(U$24-DSR-Pad10)") (class "Default")
      (node (ref "U$24") (pin "10") (pinfunction "DSR_10") (pintype "bidirectional"))
    )
    (net (code "72") (name "unconnected-(U$24-RI-Pad11)") (class "Default")
      (node (ref "U$24") (pin "11") (pinfunction "RI_11") (pintype "bidirectional"))
    )
    (net (code "73") (name "unconnected-(U$24-RS232-Pad15)") (class "Default")
      (node (ref "U$24") (pin "15") (pinfunction "RS232_15") (pintype "bidirectional"))
    )
    (net (code "74") (name "unconnected-(U1-CLK-Pad20)") (class "Default")
      (node (ref "U1") (pin "20") (pinfunction "CLK_20") (pintype "bidirectional"))
    )
    (net (code "75") (name "unconnected-(U1-CMD-Pad19)") (class "Default")
      (node (ref "U1") (pin "19") (pinfunction "CMD_19") (pintype "bidirectional"))
    )
    (net (code "76") (name "unconnected-(U1-NC-Pad32)") (class "Default")
      (node (ref "U1") (pin "32") (pinfunction "NC_32") (pintype "bidirectional"))
    )
    (net (code "77") (name "unconnected-(U1-SD1-Pad22)") (class "Default")
      (node (ref "U1") (pin "22") (pinfunction "SD1_22") (pintype "bidirectional"))
    )
    (net (code "78") (name "unconnected-(U1-SD2-Pad17)") (class "Default")
      (node (ref "U1") (pin "17") (pinfunction "SD2_17") (pintype "bidirectional"))
    )
    (net (code "79") (name "unconnected-(U1-SD3-Pad18)") (class "Default")
      (node (ref "U1") (pin "18") (pinfunction "SD3_18") (pintype "bidirectional"))
    )
    (net (code "80") (name "unconnected-(U1-SDO-Pad21)") (class "Default")
      (node (ref "U1") (pin "21") (pinfunction "SDO_21") (pintype "bidirectional"))
    )
    (net (code "81") (name "unconnected-(U2-HYS-Pad8)") (class "Default")
      (node (ref "U2") (pin "8") (pinfunction "HYS_8") (pintype "output"))
    )
    (net (code "82") (name "unconnected-(U3-*OUT-Pad4)") (class "Default")
      (node (ref "U3") (pin "4") (pinfunction "*OUT_4") (pintype "output"))
    )
    (net (code "83") (name "unconnected-(X6-PadID)") (class "Default")
      (node (ref "X6") (pin "ID") (pinfunction "ID_ID") (pintype "bidirectional"))
    )
  )
)
